# teensyRecord.net
KiCad netlist of a schematic drawn in Altium Designer
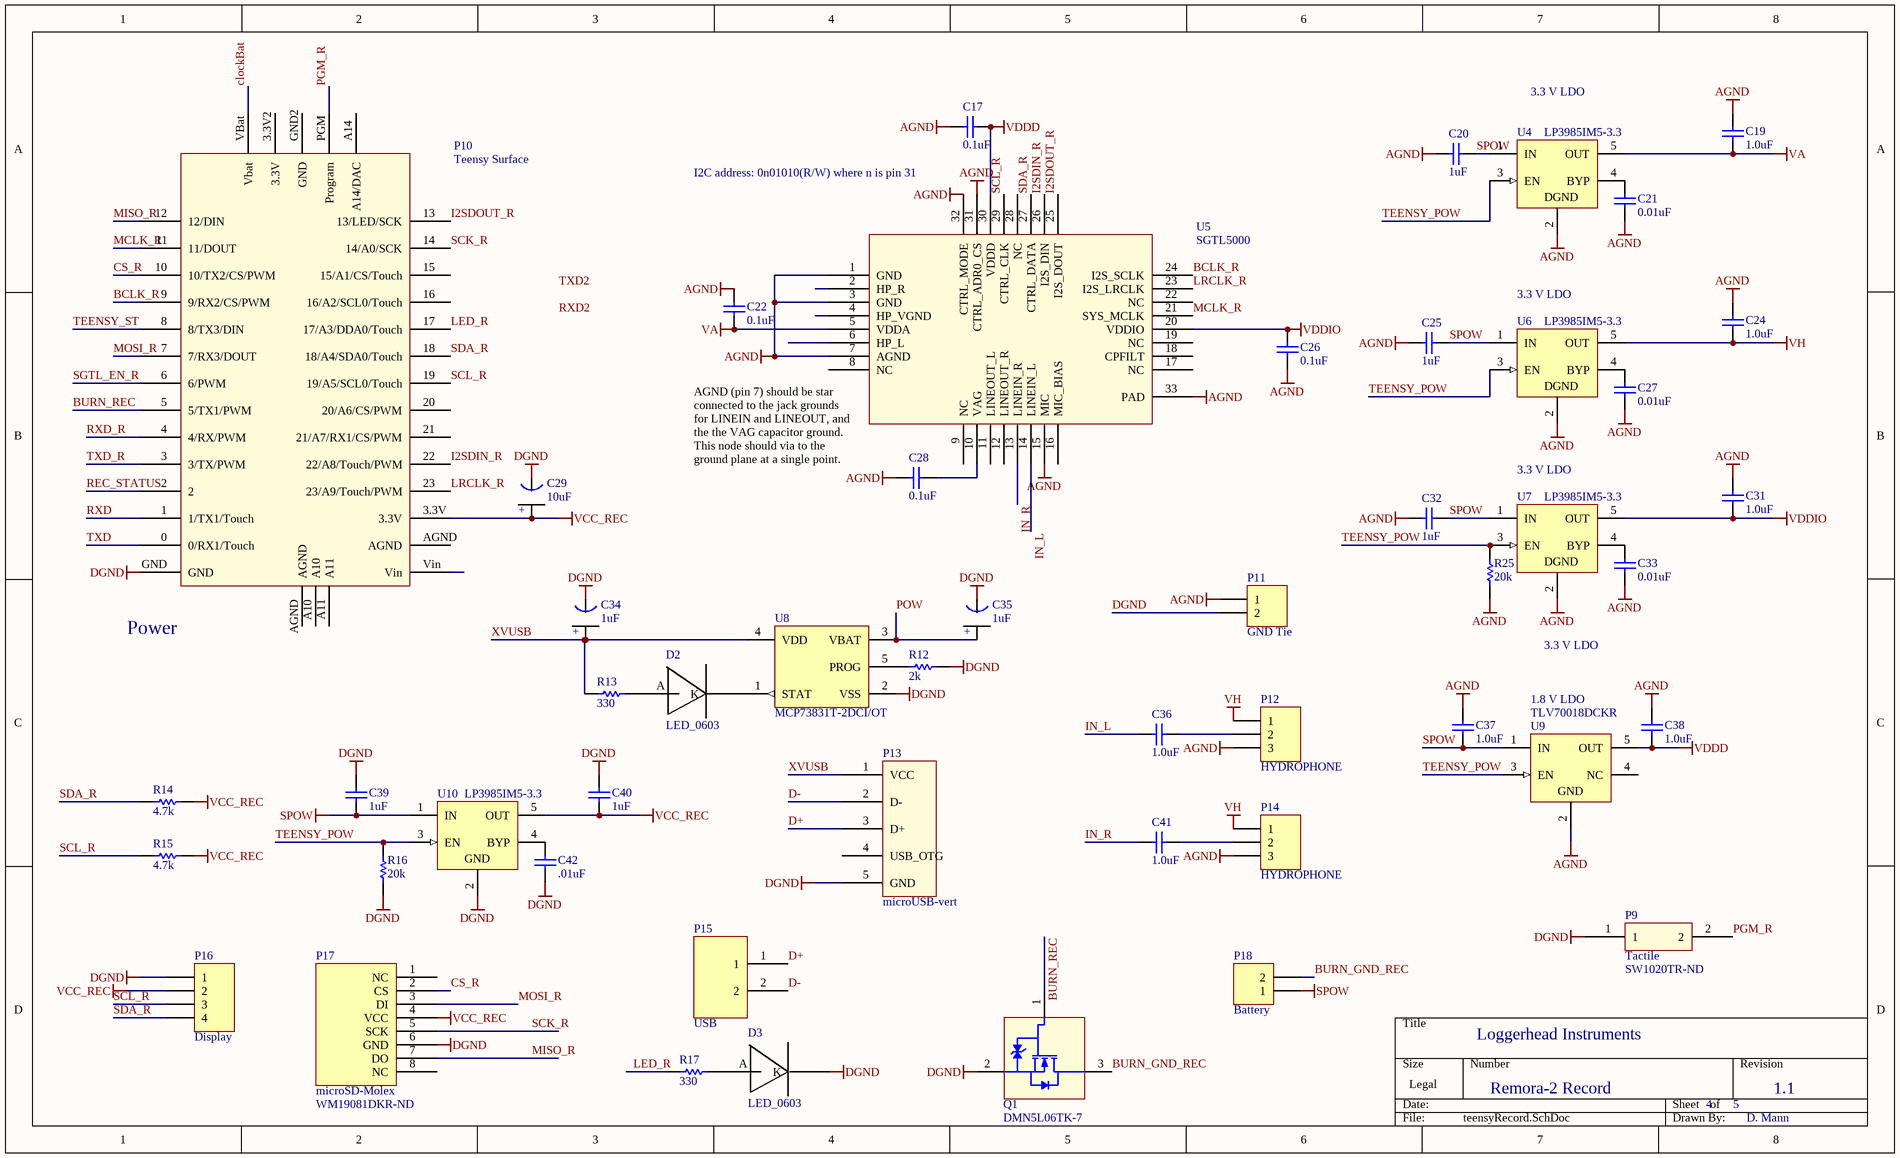
[diagram p0: teensyRecord.SchDoc]

(export (version "E")
  (design (tool "Eeschema 10.0.6"))
  (components
    (comp (ref "C17")
      (value "0.1uF")
      (footprint "0402")
      (description "Ceramic Chip Capacitor - Standard")
      (fields (field (name "PUBLISHER") "Altium Limited"))
      (libsource (lib "KEMET Chip Capacitor") (part "C0402"))
    )
    (comp (ref "C19")
      (value "1.0uF")
      (footprint "0402")
      (description "Ceramic Chip Capacitor - Standard")
      (fields (field (name "PUBLISHER") "Altium Limited"))
      (libsource (lib "KEMET Chip Capacitor") (part "C0402"))
    )
    (comp (ref "C20")
      (value "1uF")
      (footprint "0402")
      (description "Ceramic Chip Capacitor - Standard")
      (fields (field (name "PUBLISHER") "Altium Limited"))
      (libsource (lib "KEMET Chip Capacitor") (part "C0402"))
    )
    (comp (ref "C21")
      (value "0.01uF")
      (footprint "0402")
      (description "Ceramic Chip Capacitor - Standard")
      (fields (field (name "PUBLISHER") "Altium Limited"))
      (libsource (lib "KEMET Chip Capacitor") (part "C0402"))
    )
    (comp (ref "C22")
      (value "0.1uF")
      (footprint "0402")
      (description "Ceramic Chip Capacitor - Standard")
      (fields (field (name "PUBLISHER") "Altium Limited"))
      (libsource (lib "KEMET Chip Capacitor") (part "C0402"))
    )
    (comp (ref "C24")
      (value "1.0uF")
      (footprint "0402")
      (description "Ceramic Chip Capacitor - Standard")
      (fields (field (name "PUBLISHER") "Altium Limited"))
      (libsource (lib "KEMET Chip Capacitor") (part "C0402"))
    )
    (comp (ref "C25")
      (value "1uF")
      (footprint "0402")
      (description "Ceramic Chip Capacitor - Standard")
      (fields (field (name "PUBLISHER") "Altium Limited"))
      (libsource (lib "KEMET Chip Capacitor") (part "C0402"))
    )
    (comp (ref "C26")
      (value "0.1uF")
      (footprint "0402")
      (description "Ceramic Chip Capacitor - Standard")
      (fields (field (name "PUBLISHER") "Altium Limited"))
      (libsource (lib "KEMET Chip Capacitor") (part "C0402"))
    )
    (comp (ref "C27")
      (value "0.01uF")
      (footprint "0402")
      (description "Ceramic Chip Capacitor - Standard")
      (fields (field (name "PUBLISHER") "Altium Limited"))
      (libsource (lib "KEMET Chip Capacitor") (part "C0402"))
    )
    (comp (ref "C28")
      (value "0.1uF")
      (footprint "0402")
      (description "Ceramic Chip Capacitor - Standard")
      (fields (field (name "PUBLISHER") "Altium Limited"))
      (libsource (lib "KEMET Chip Capacitor") (part "C0402"))
    )
    (comp (ref "C29") (value "10uF") (footprint "Tant0805") (libsource (lib "Loggerhead") (part "Tant0805")))
    (comp (ref "C31")
      (value "1.0uF")
      (footprint "0402")
      (description "Ceramic Chip Capacitor - Standard")
      (fields (field (name "PUBLISHER") "Altium Limited"))
      (libsource (lib "KEMET Chip Capacitor") (part "C0402"))
    )
    (comp (ref "C32")
      (value "1uF")
      (footprint "0402")
      (description "Ceramic Chip Capacitor - Standard")
      (fields (field (name "PUBLISHER") "Altium Limited"))
      (libsource (lib "KEMET Chip Capacitor") (part "C0402"))
    )
    (comp (ref "C33")
      (value "0.01uF")
      (footprint "0402")
      (description "Ceramic Chip Capacitor - Standard")
      (fields (field (name "PUBLISHER") "Altium Limited"))
      (libsource (lib "KEMET Chip Capacitor") (part "C0402"))
    )
    (comp (ref "C34") (value "1uF") (footprint "Tant0805") (libsource (lib "Loggerhead") (part "Tant0805")))
    (comp (ref "C35") (value "1uF") (footprint "Tant0805") (libsource (lib "Loggerhead") (part "Tant0805")))
    (comp (ref "C36")
      (value "1.0uF")
      (footprint "0402")
      (description "Ceramic Chip Capacitor - Standard")
      (fields (field (name "PUBLISHER") "Altium Limited"))
      (libsource (lib "KEMET Chip Capacitor") (part "C0402"))
    )
    (comp (ref "C37")
      (value "1.0uF")
      (footprint "0402")
      (description "Ceramic Chip Capacitor - Standard")
      (fields (field (name "PUBLISHER") "Altium Limited"))
      (libsource (lib "KEMET Chip Capacitor") (part "C0402"))
    )
    (comp (ref "C38")
      (value "1.0uF")
      (footprint "0402")
      (description "Ceramic Chip Capacitor - Standard")
      (fields (field (name "PUBLISHER") "Altium Limited"))
      (libsource (lib "KEMET Chip Capacitor") (part "C0402"))
    )
    (comp (ref "C39")
      (value "1uF")
      (footprint "0402")
      (description "Ceramic Chip Capacitor - Standard")
      (fields (field (name "PUBLISHER") "Altium Limited"))
      (libsource (lib "KEMET Chip Capacitor") (part "C0402"))
    )
    (comp (ref "C40")
      (value "1uF")
      (footprint "0402")
      (description "Ceramic Chip Capacitor - Standard")
      (fields (field (name "PUBLISHER") "Altium Limited"))
      (libsource (lib "KEMET Chip Capacitor") (part "C0402"))
    )
    (comp (ref "C41")
      (value "1.0uF")
      (footprint "0402")
      (description "Ceramic Chip Capacitor - Standard")
      (fields (field (name "PUBLISHER") "Altium Limited"))
      (libsource (lib "KEMET Chip Capacitor") (part "C0402"))
    )
    (comp (ref "C42")
      (value ".01uF")
      (footprint "0402")
      (description "Ceramic Chip Capacitor - Standard")
      (fields (field (name "PUBLISHER") "Altium Limited"))
      (libsource (lib "KEMET Chip Capacitor") (part "C0402"))
    )
    (comp (ref "D2")
      (value "LED_0603")
      (footprint "Diode0603")
      (libsource (lib "Loggerhead") (part "LED_0603"))
    )
    (comp (ref "D3")
      (value "LED_0603")
      (footprint "Diode0603")
      (libsource (lib "Loggerhead") (part "LED_0603"))
    )
    (comp (ref "P9")
      (value "Tactile")
      (footprint "Tactile-B3U-1000")
      (fields (field (name "SUPPLIER PART NUMBER 1") "SW1020TR-ND"))
      (libsource (lib "Loggerhead") (part "Tactile_B3U-1000"))
    )
    (comp (ref "P10")
      (value "Teensy Surface")
      (footprint "TEENSY3.2_surface_mount")
      (libsource (lib "Teensy") (part "Teensy3.2_surface_mount"))
    )
    (comp (ref "P11")
      (value "GND Tie")
      (footprint "HDR1X2")
      (description "Header, 2-Pin")
      (fields (field (name "PUBLISHER") "Altium Limited"))
      (libsource (lib "Miscellaneous Connectors") (part "Header 2"))
    )
    (comp (ref "P12")
      (value "HYDROPHONE")
      (footprint "HDR1X3")
      (description "Header, 3-Pin")
      (fields (field (name "PUBLISHER") "Altium Limited"))
      (libsource (lib "Miscellaneous Connectors") (part "Header 3"))
    )
    (comp (ref "P13")
      (value "microUSB-vert")
      (footprint "MICROUSB-VERT")
      (description "Molex 105133-0011")
      (libsource (lib "Loggerhead") (part "microUSB-vert"))
    )
    (comp (ref "P14")
      (value "HYDROPHONE")
      (footprint "HDR1X3")
      (description "Header, 3-Pin")
      (fields (field (name "PUBLISHER") "Altium Limited"))
      (libsource (lib "Miscellaneous Connectors") (part "Header 3"))
    )
    (comp (ref "P15")
      (value "USB")
      (footprint "HDR_2x1_2mm")
      (description "Charging Connector")
      (libsource (lib "Loggerhead") (part "HDR_2x1_2mm"))
    )
    (comp (ref "P16")
      (value "Display")
      (footprint "HDR1X4")
      (description "Header, 4-Pin")
      (fields (field (name "PUBLISHER") "Altium Limited"))
      (libsource (lib "Miscellaneous Connectors") (part "Header 4"))
    )
    (comp (ref "P17")
      (value "microSD-Molex")
      (footprint "microSD_Molex_hinged")
      (fields (field (name "SUPPLIER PART NUMBER 1") "WM19081DKR-ND"))
      (libsource (lib "Loggerhead") (part "microSD_Molex_hinged"))
    )
    (comp (ref "P18")
      (value "Battery")
      (footprint "HDR1X2")
      (description "Header, 2-Pin")
      (fields (field (name "PUBLISHER") "Altium Limited"))
      (libsource (lib "") (part "Header 2_1"))
    )
    (comp (ref "Q1")
      (value "DMN5L06TK-7")
      (footprint "SOT-523")
      (description "Ultra-low leakage Enhanced MOSFET")
      (fields
        (field (name "CREATOR AND DATE") "Will Flanery 2010-09-02")
        (field (name "FOOTPRINT VERIFIED BY") "*")
        (field (name "SCHEMATIC VERIFIED BY") "*")
        (field (name "VENDOR INFO VERIFIED BY") "*")
      )
      (libsource (lib "Flanery") (part "FET DMN5L06TK-7"))
    )
    (comp (ref "R12")
      (value "2k")
      (footprint "3-0603")
      (fields (field (name "PUBLISHER") "Altium Limited"))
      (libsource (lib "Panasonic Resistor") (part "ERJ3RK"))
    )
    (comp (ref "R13")
      (value "330")
      (footprint "3-0603")
      (fields (field (name "PUBLISHER") "Altium Limited"))
      (libsource (lib "Panasonic Resistor") (part "ERJ3RK"))
    )
    (comp (ref "R14")
      (value "4.7k")
      (footprint "3-0603")
      (fields (field (name "PUBLISHER") "Altium Limited"))
      (libsource (lib "Panasonic Resistor") (part "ERJ3RK"))
    )
    (comp (ref "R15")
      (value "4.7k")
      (footprint "3-0603")
      (fields (field (name "PUBLISHER") "Altium Limited"))
      (libsource (lib "Panasonic Resistor") (part "ERJ3RK"))
    )
    (comp (ref "R16")
      (value "20k")
      (footprint "3-0603")
      (fields (field (name "PUBLISHER") "Altium Limited"))
      (libsource (lib "Panasonic Resistor") (part "ERJ3RK"))
    )
    (comp (ref "R17")
      (value "330")
      (footprint "3-0603")
      (fields (field (name "PUBLISHER") "Altium Limited"))
      (libsource (lib "Panasonic Resistor") (part "ERJ3RK"))
    )
    (comp (ref "R25")
      (value "20k")
      (footprint "3-0603")
      (fields (field (name "PUBLISHER") "Altium Limited"))
      (libsource (lib "Panasonic Resistor") (part "ERJ3RK"))
    )
    (comp (ref "U4")
      (value "LP3985IM5-3.3")
      (footprint "MF05A_N")
      (description "Micropower, 150mA Low-Noise Ultra Low-Dropout CMOS Voltage Regulator")
      (fields
        (field (name "MANUFACTURER") "National Semiconductor")
        (field (name "DIGIKEYPARTNUMBER") "LP3985IM5-3.3CT-ND")
        (field (name "PUBLISHER") "Altium Limited")
      )
      (libsource (lib "NSC LDO") (part "LP3985IM5-3.3"))
    )
    (comp (ref "U5") (value "SGTL5000") (footprint "QFN32") (libsource (lib "Loggerhead") (part "SGTL5000")))
    (comp (ref "U6")
      (value "LP3985IM5-3.3")
      (footprint "MF05A_N")
      (description "Micropower, 150mA Low-Noise Ultra Low-Dropout CMOS Voltage Regulator")
      (fields
        (field (name "MANUFACTURER") "National Semiconductor")
        (field (name "DIGIKEYPARTNUMBER") "LP3985IM5-3.3CT-ND")
        (field (name "PUBLISHER") "Altium Limited")
      )
      (libsource (lib "NSC LDO") (part "LP3985IM5-3.3"))
    )
    (comp (ref "U7")
      (value "LP3985IM5-3.3")
      (footprint "MF05A_N")
      (description "Micropower, 150mA Low-Noise Ultra Low-Dropout CMOS Voltage Regulator")
      (fields
        (field (name "MANUFACTURER") "National Semiconductor")
        (field (name "DIGIKEYPARTNUMBER") "LP3985IM5-3.3CT-ND")
        (field (name "PUBLISHER") "Altium Limited")
      )
      (libsource (lib "NSC LDO") (part "LP3985IM5-3.3"))
    )
    (comp (ref "U8")
      (value "MCP73831T-2DCI/OT")
      (footprint "SOT-23-OT5_N")
      (libsource (lib "Microchip Power Management Battery Management") (part "MCP73831T-2DCI/OT"))
    )
    (comp (ref "U9")
      (value "TLV70018DCKR")
      (footprint "TI-DCK5_V")
      (fields (field (name "MANUFACTURER") "Texas Instruments"))
      (libsource (lib "TI Power Management Linear Regulator Single Channel LDO (0-350mA)") (part "TLV70018DCKR"))
    )
    (comp (ref "U10")
      (value "LP3985IM5-3.3")
      (footprint "MF05A_N")
      (description "Micropower, 150mA Low-Noise Ultra Low-Dropout CMOS Voltage Regulator")
      (fields
        (field (name "MANUFACTURER") "National Semiconductor")
        (field (name "DIGIKEYPARTNUMBER") "LP3985IM5-3.3CT-ND")
        (field (name "PUBLISHER") "Altium Limited")
      )
      (libsource (lib "NSC LDO") (part "LP3985IM5-3.3"))
    )
  )
  (nets
    (net (code "1") (name "/BCLK_R") (class "Default")
      (node (ref "P10") (pin "9") (pinfunction "9/RX2/CS/PWM_9") (pintype "passive"))
      (node (ref "U5") (pin "24") (pinfunction "I2S_SCLK_24") (pintype "passive"))
    )
    (net (code "2") (name "/BURN_GND_REC") (class "Default")
      (node (ref "P18") (pin "2") (pinfunction "2_2") (pintype "passive"))
      (node (ref "Q1") (pin "3") (pinfunction "D_3") (pintype "passive"))
    )
    (net (code "3") (name "/BURN_REC") (class "Default")
      (node (ref "P10") (pin "5") (pinfunction "5/TX1/PWM_5") (pintype "passive"))
      (node (ref "Q1") (pin "1") (pinfunction "G_1") (pintype "passive"))
    )
    (net (code "4") (name "/CS_R") (class "Default")
      (node (ref "P10") (pin "10") (pinfunction "10/TX2/CS/PWM_10") (pintype "passive"))
      (node (ref "P17") (pin "2") (pinfunction "CS_2") (pintype "passive"))
    )
    (net (code "5") (name "/D+") (class "Default")
      (node (ref "P13") (pin "3") (pinfunction "D+_3") (pintype "passive"))
      (node (ref "P15") (pin "1") (pinfunction "1_1") (pintype "passive"))
    )
    (net (code "6") (name "/D-") (class "Default")
      (node (ref "P13") (pin "2") (pinfunction "D-_2") (pintype "passive"))
      (node (ref "P15") (pin "2") (pinfunction "2_2") (pintype "passive"))
    )
    (net (code "7") (name "/I2SDIN_R") (class "Default")
      (node (ref "P10") (pin "22") (pinfunction "22/A8/Touch/PWM_22") (pintype "passive"))
      (node (ref "U5") (pin "26") (pinfunction "I2S_DIN_26") (pintype "passive"))
    )
    (net (code "8") (name "/I2SDOUT_R") (class "Default")
      (node (ref "P10") (pin "13") (pinfunction "13/LED/SCK_13") (pintype "passive"))
      (node (ref "U5") (pin "25") (pinfunction "I2S_DOUT_25") (pintype "passive"))
    )
    (net (code "9") (name "/IN_L") (class "Default")
      (node (ref "C36") (pin "2") (pinfunction "2_2") (pintype "passive"))
      (node (ref "U5") (pin "14") (pinfunction "LINEIN_L_14") (pintype "passive"))
    )
    (net (code "10") (name "/IN_R") (class "Default")
      (node (ref "C41") (pin "2") (pinfunction "2_2") (pintype "passive"))
      (node (ref "U5") (pin "13") (pinfunction "LINEIN_R_13") (pintype "passive"))
    )
    (net (code "11") (name "/LED_R") (class "Default")
      (node (ref "P10") (pin "17") (pinfunction "17/A3/DDA0/Touch_17") (pintype "passive"))
      (node (ref "R17") (pin "1") (pinfunction "1_1") (pintype "passive"))
    )
    (net (code "12") (name "/LRCLK_R") (class "Default")
      (node (ref "P10") (pin "23") (pinfunction "23/A9/Touch/PWM_23") (pintype "passive"))
      (node (ref "U5") (pin "23") (pinfunction "I2S_LRCLK_23") (pintype "passive"))
    )
    (net (code "13") (name "/MCLK_R") (class "Default")
      (node (ref "P10") (pin "11") (pinfunction "11/DOUT_11") (pintype "passive"))
      (node (ref "U5") (pin "21") (pinfunction "SYS_MCLK_21") (pintype "passive"))
    )
    (net (code "14") (name "/MISO_R") (class "Default")
      (node (ref "P10") (pin "12") (pinfunction "12/DIN_12") (pintype "passive"))
      (node (ref "P17") (pin "7") (pinfunction "DO_7") (pintype "passive"))
    )
    (net (code "15") (name "/MOSI_R") (class "Default")
      (node (ref "P10") (pin "7") (pinfunction "7/RX3/DOUT_7") (pintype "passive"))
      (node (ref "P17") (pin "3") (pinfunction "DI_3") (pintype "passive"))
    )
    (net (code "16") (name "/PGM_R") (class "Default")
      (node (ref "P10") (pin "PGM") (pinfunction "Program_PGM") (pintype "passive"))
      (node (ref "P9") (pin "2") (pinfunction "2_2") (pintype "passive"))
    )
    (net (code "17") (name "/POW") (class "Default")
      (node (ref "C35") (pin "2") (pinfunction "+_2") (pintype "passive"))
      (node (ref "U8") (pin "3") (pinfunction "VBAT_3") (pintype "power_in"))
    )
    (net (code "18") (name "/REC_STATUS") (class "Default")
      (node (ref "P10") (pin "2") (pinfunction "2_2") (pintype "passive"))
    )
    (net (code "19") (name "/RXD") (class "Default")
      (node (ref "P10") (pin "1") (pinfunction "1/TX1/Touch_1") (pintype "passive"))
    )
    (net (code "21") (name "/RXD_R") (class "Default")
      (node (ref "P10") (pin "4") (pinfunction "4/RX/PWM_4") (pintype "passive"))
    )
    (net (code "22") (name "/SCK_R") (class "Default")
      (node (ref "P10") (pin "14") (pinfunction "14/A0/SCK_14") (pintype "passive"))
      (node (ref "P17") (pin "5") (pinfunction "SCK_5") (pintype "passive"))
    )
    (net (code "23") (name "/SCL_R") (class "Default")
      (node (ref "P10") (pin "19") (pinfunction "19/A5/SCL0/Touch_19") (pintype "passive"))
      (node (ref "P16") (pin "3") (pinfunction "3_3") (pintype "passive"))
      (node (ref "R15") (pin "1") (pinfunction "1_1") (pintype "passive"))
      (node (ref "U5") (pin "29") (pinfunction "CTRL_CLK_29") (pintype "passive"))
    )
    (net (code "24") (name "/SDA_R") (class "Default")
      (node (ref "P10") (pin "18") (pinfunction "18/A4/SDA0/Touch_18") (pintype "passive"))
      (node (ref "P16") (pin "4") (pinfunction "4_4") (pintype "passive"))
      (node (ref "R14") (pin "1") (pinfunction "1_1") (pintype "passive"))
      (node (ref "U5") (pin "27") (pinfunction "CTRL_DATA_27") (pintype "passive"))
    )
    (net (code "25") (name "/SGTL_EN_R") (class "Default")
      (node (ref "P10") (pin "6") (pinfunction "6/PWM_6") (pintype "passive"))
    )
    (net (code "26") (name "/TEENSY_POW") (class "Default")
      (node (ref "R16") (pin "2") (pinfunction "2_2") (pintype "passive"))
      (node (ref "R25") (pin "1") (pinfunction "1_1") (pintype "passive"))
      (node (ref "U10") (pin "3") (pinfunction "EN_3") (pintype "input"))
      (node (ref "U4") (pin "3") (pinfunction "EN_3") (pintype "input"))
      (node (ref "U6") (pin "3") (pinfunction "EN_3") (pintype "input"))
      (node (ref "U7") (pin "3") (pinfunction "EN_3") (pintype "input"))
      (node (ref "U9") (pin "3") (pinfunction "EN_3") (pintype "input"))
    )
    (net (code "27") (name "/TEENSY_ST") (class "Default")
      (node (ref "P10") (pin "8") (pinfunction "8/TX3/DIN_8") (pintype "passive"))
    )
    (net (code "28") (name "/TXD") (class "Default")
      (node (ref "P10") (pin "0") (pinfunction "0/RX1/Touch_0") (pintype "passive"))
    )
    (net (code "30") (name "/TXD_R") (class "Default")
      (node (ref "P10") (pin "3") (pinfunction "3/TX/PWM_3") (pintype "passive"))
    )
    (net (code "31") (name "/XVUSB") (class "Default")
      (node (ref "C34") (pin "2") (pinfunction "+_2") (pintype "passive"))
      (node (ref "P13") (pin "1") (pinfunction "VCC_1") (pintype "passive"))
      (node (ref "R13") (pin "1") (pinfunction "1_1") (pintype "passive"))
      (node (ref "U8") (pin "4") (pinfunction "VDD_4") (pintype "power_in"))
    )
    (net (code "32") (name "/clockBat") (class "Default")
      (node (ref "P10") (pin "VBat") (pinfunction "Vbat_VBat") (pintype "passive"))
    )
    (net (code "33") (name "AGND") (class "Default")
      (node (ref "C17") (pin "2") (pinfunction "2_2") (pintype "passive"))
      (node (ref "C19") (pin "2") (pinfunction "2_2") (pintype "passive"))
      (node (ref "C20") (pin "2") (pinfunction "2_2") (pintype "passive"))
      (node (ref "C21") (pin "2") (pinfunction "2_2") (pintype "passive"))
      (node (ref "C22") (pin "2") (pinfunction "2_2") (pintype "passive"))
      (node (ref "C24") (pin "2") (pinfunction "2_2") (pintype "passive"))
      (node (ref "C25") (pin "2") (pinfunction "2_2") (pintype "passive"))
      (node (ref "C26") (pin "2") (pinfunction "2_2") (pintype "passive"))
      (node (ref "C27") (pin "2") (pinfunction "2_2") (pintype "passive"))
      (node (ref "C28") (pin "2") (pinfunction "2_2") (pintype "passive"))
      (node (ref "C31") (pin "2") (pinfunction "2_2") (pintype "passive"))
      (node (ref "C32") (pin "2") (pinfunction "2_2") (pintype "passive"))
      (node (ref "C33") (pin "2") (pinfunction "2_2") (pintype "passive"))
      (node (ref "C37") (pin "2") (pinfunction "2_2") (pintype "passive"))
      (node (ref "C38") (pin "2") (pinfunction "2_2") (pintype "passive"))
      (node (ref "P11") (pin "1") (pinfunction "1_1") (pintype "passive"))
      (node (ref "P12") (pin "3") (pinfunction "3_3") (pintype "passive"))
      (node (ref "P14") (pin "3") (pinfunction "3_3") (pintype "passive"))
      (node (ref "R25") (pin "2") (pinfunction "2_2") (pintype "passive"))
      (node (ref "U4") (pin "2") (pinfunction "GND_2") (pintype "power_in"))
      (node (ref "U5") (pin "1") (pinfunction "GND_1") (pintype "passive"))
      (node (ref "U5") (pin "15") (pinfunction "MIC_15") (pintype "passive"))
      (node (ref "U5") (pin "3") (pinfunction "GND_3") (pintype "passive"))
      (node (ref "U5") (pin "31") (pinfunction "CTRL_ADR0_CS_31") (pintype "passive"))
      (node (ref "U5") (pin "32") (pinfunction "CTRL_MODE_32") (pintype "passive"))
      (node (ref "U5") (pin "33") (pinfunction "PAD_33") (pintype "passive"))
      (node (ref "U5") (pin "7") (pinfunction "AGND_7") (pintype "passive"))
      (node (ref "U6") (pin "2") (pinfunction "GND_2") (pintype "power_in"))
      (node (ref "U7") (pin "2") (pinfunction "GND_2") (pintype "power_in"))
      (node (ref "U9") (pin "2") (pinfunction "GND_2") (pintype "power_in"))
    )
    (net (code "34") (name "DGND") (class "Default")
      (node (ref "C29") (pin "1") (pinfunction "GND_1") (pintype "passive"))
      (node (ref "C34") (pin "1") (pinfunction "GND_1") (pintype "passive"))
      (node (ref "C35") (pin "1") (pinfunction "GND_1") (pintype "passive"))
      (node (ref "C39") (pin "2") (pinfunction "2_2") (pintype "passive"))
      (node (ref "C40") (pin "2") (pinfunction "2_2") (pintype "passive"))
      (node (ref "C42") (pin "1") (pinfunction "1_1") (pintype "passive"))
      (node (ref "D3") (pin "K") (pinfunction "K_K") (pintype "passive"))
      (node (ref "P10") (pin "GND") (pinfunction "GND_GND") (pintype "passive"))
      (node (ref "P11") (pin "2") (pinfunction "2_2") (pintype "passive"))
      (node (ref "P13") (pin "5") (pinfunction "GND_5") (pintype "passive"))
      (node (ref "P16") (pin "1") (pinfunction "1_1") (pintype "passive"))
      (node (ref "P17") (pin "6") (pinfunction "GND_6") (pintype "passive"))
      (node (ref "P9") (pin "1") (pinfunction "1_1") (pintype "passive"))
      (node (ref "Q1") (pin "2") (pinfunction "S_2") (pintype "passive"))
      (node (ref "R12") (pin "1") (pinfunction "1_1") (pintype "passive"))
      (node (ref "R16") (pin "1") (pinfunction "1_1") (pintype "passive"))
      (node (ref "U10") (pin "2") (pinfunction "GND_2") (pintype "power_in"))
      (node (ref "U8") (pin "2") (pinfunction "VSS_2") (pintype "power_in"))
    )
    (net (code "35") (name "Net-(C36-Pad1)") (class "Default")
      (node (ref "C36") (pin "1") (pinfunction "1_1") (pintype "passive"))
      (node (ref "P12") (pin "2") (pinfunction "2_2") (pintype "passive"))
    )
    (net (code "36") (name "Net-(C41-Pad1)") (class "Default")
      (node (ref "C41") (pin "1") (pinfunction "1_1") (pintype "passive"))
      (node (ref "P14") (pin "2") (pinfunction "2_2") (pintype "passive"))
    )
    (net (code "37") (name "Net-(D2-PadA)") (class "Default")
      (node (ref "D2") (pin "A") (pinfunction "A_A") (pintype "passive"))
      (node (ref "R13") (pin "2") (pinfunction "2_2") (pintype "passive"))
    )
    (net (code "38") (name "Net-(D3-PadA)") (class "Default")
      (node (ref "D3") (pin "A") (pinfunction "A_A") (pintype "passive"))
      (node (ref "R17") (pin "2") (pinfunction "2_2") (pintype "passive"))
    )
    (net (code "39") (name "Net-(U4-BYP)") (class "Default")
      (node (ref "C21") (pin "1") (pinfunction "1_1") (pintype "passive"))
      (node (ref "U4") (pin "4") (pinfunction "BYP_4") (pintype "passive"))
    )
    (net (code "40") (name "Net-(U5-VAG)") (class "Default")
      (node (ref "C28") (pin "1") (pinfunction "1_1") (pintype "passive"))
      (node (ref "U5") (pin "10") (pinfunction "VAG_10") (pintype "passive"))
    )
    (net (code "41") (name "Net-(U6-BYP)") (class "Default")
      (node (ref "C27") (pin "1") (pinfunction "1_1") (pintype "passive"))
      (node (ref "U6") (pin "4") (pinfunction "BYP_4") (pintype "passive"))
    )
    (net (code "42") (name "Net-(U7-BYP)") (class "Default")
      (node (ref "C33") (pin "1") (pinfunction "1_1") (pintype "passive"))
      (node (ref "U7") (pin "4") (pinfunction "BYP_4") (pintype "passive"))
    )
    (net (code "43") (name "Net-(U8-PROG)") (class "Default")
      (node (ref "R12") (pin "2") (pinfunction "2_2") (pintype "passive"))
      (node (ref "U8") (pin "5") (pinfunction "PROG_5") (pintype "passive"))
    )
    (net (code "44") (name "Net-(U8-STAT)") (class "Default")
      (node (ref "D2") (pin "K") (pinfunction "K_K") (pintype "passive"))
      (node (ref "U8") (pin "1") (pinfunction "STAT_1") (pintype "output"))
    )
    (net (code "45") (name "Net-(U10-BYP)") (class "Default")
      (node (ref "C42") (pin "2") (pinfunction "2_2") (pintype "passive"))
      (node (ref "U10") (pin "4") (pinfunction "BYP_4") (pintype "passive"))
    )
    (net (code "46") (name "SPOW") (class "Default")
      (node (ref "C20") (pin "1") (pinfunction "1_1") (pintype "passive"))
      (node (ref "C25") (pin "1") (pinfunction "1_1") (pintype "passive"))
      (node (ref "C32") (pin "1") (pinfunction "1_1") (pintype "passive"))
      (node (ref "C37") (pin "1") (pinfunction "1_1") (pintype "passive"))
      (node (ref "C39") (pin "1") (pinfunction "1_1") (pintype "passive"))
      (node (ref "P18") (pin "1") (pinfunction "1_1") (pintype "passive"))
      (node (ref "U10") (pin "1") (pinfunction "IN_1") (pintype "power_in"))
      (node (ref "U4") (pin "1") (pinfunction "IN_1") (pintype "power_in"))
      (node (ref "U6") (pin "1") (pinfunction "IN_1") (pintype "power_in"))
      (node (ref "U7") (pin "1") (pinfunction "IN_1") (pintype "power_in"))
      (node (ref "U9") (pin "1") (pinfunction "IN_1") (pintype "power_in"))
    )
    (net (code "47") (name "VA") (class "Default")
      (node (ref "C19") (pin "1") (pinfunction "1_1") (pintype "passive"))
      (node (ref "C22") (pin "1") (pinfunction "1_1") (pintype "passive"))
      (node (ref "U4") (pin "5") (pinfunction "OUT_5") (pintype "power_in"))
      (node (ref "U5") (pin "5") (pinfunction "VDDA_5") (pintype "passive"))
    )
    (net (code "48") (name "VCC_REC") (class "Default")
      (node (ref "C29") (pin "2") (pinfunction "+_2") (pintype "passive"))
      (node (ref "C40") (pin "1") (pinfunction "1_1") (pintype "passive"))
      (node (ref "P10") (pin "3.3V") (pinfunction "3.3V_3.3V") (pintype "passive"))
      (node (ref "P16") (pin "2") (pinfunction "2_2") (pintype "passive"))
      (node (ref "P17") (pin "4") (pinfunction "VCC_4") (pintype "passive"))
      (node (ref "R14") (pin "2") (pinfunction "2_2") (pintype "passive"))
      (node (ref "R15") (pin "2") (pinfunction "2_2") (pintype "passive"))
      (node (ref "U10") (pin "5") (pinfunction "OUT_5") (pintype "power_in"))
    )
    (net (code "49") (name "VDDD") (class "Default")
      (node (ref "C17") (pin "1") (pinfunction "1_1") (pintype "passive"))
      (node (ref "C38") (pin "1") (pinfunction "1_1") (pintype "passive"))
      (node (ref "U5") (pin "30") (pinfunction "VDDD_30") (pintype "passive"))
      (node (ref "U9") (pin "5") (pinfunction "OUT_5") (pintype "power_in"))
    )
    (net (code "50") (name "VDDIO") (class "Default")
      (node (ref "C26") (pin "1") (pinfunction "1_1") (pintype "passive"))
      (node (ref "C31") (pin "1") (pinfunction "1_1") (pintype "passive"))
      (node (ref "U5") (pin "20") (pinfunction "VDDIO_20") (pintype "passive"))
      (node (ref "U7") (pin "5") (pinfunction "OUT_5") (pintype "power_in"))
    )
    (net (code "51") (name "VH") (class "Default")
      (node (ref "C24") (pin "1") (pinfunction "1_1") (pintype "passive"))
      (node (ref "P12") (pin "1") (pinfunction "1_1") (pintype "passive"))
      (node (ref "P14") (pin "1") (pinfunction "1_1") (pintype "passive"))
      (node (ref "U6") (pin "5") (pinfunction "OUT_5") (pintype "power_in"))
    )
    (net (code "52") (name "unconnected-(P10-3.3V-Pad3.3V2)") (class "Default")
      (node (ref "P10") (pin "3.3V2") (pinfunction "3.3V_3.3V2") (pintype "passive"))
    )
    (net (code "53") (name "unconnected-(P10-15{slash}A1{slash}CS{slash}Touch-Pad15)") (class "Default")
      (node (ref "P10") (pin "15") (pinfunction "15/A1/CS/Touch_15") (pintype "passive"))
    )
    (net (code "54") (name "unconnected-(P10-16{slash}A2{slash}SCL0{slash}Touch-Pad16)") (class "Default")
      (node (ref "P10") (pin "16") (pinfunction "16/A2/SCL0/Touch_16") (pintype "passive"))
    )
    (net (code "55") (name "unconnected-(P10-20{slash}A6{slash}CS{slash}PWM-Pad20)") (class "Default")
      (node (ref "P10") (pin "20") (pinfunction "20/A6/CS/PWM_20") (pintype "passive"))
    )
    (net (code "56") (name "unconnected-(P10-21{slash}A7{slash}RX1{slash}CS{slash}PWM-Pad21)") (class "Default")
      (node (ref "P10") (pin "21") (pinfunction "21/A7/RX1/CS/PWM_21") (pintype "passive"))
    )
    (net (code "57") (name "unconnected-(P10-A14{slash}DAC-PadA14)") (class "Default")
      (node (ref "P10") (pin "A14") (pinfunction "A14/DAC_A14") (pintype "passive"))
    )
    (net (code "58") (name "unconnected-(P10-GND-PadGND2)") (class "Default")
      (node (ref "P10") (pin "GND2") (pinfunction "GND_GND2") (pintype "passive"))
    )
    (net (code "59") (name "unconnected-(P10-PadA10)") (class "Default")
      (node (ref "P10") (pin "A10") (pinfunction "A10_A10") (pintype "passive"))
    )
    (net (code "60") (name "unconnected-(P10-PadA11)") (class "Default")
      (node (ref "P10") (pin "A11") (pinfunction "A11_A11") (pintype "passive"))
    )
    (net (code "61") (name "unconnected-(P10-PadAGND)") (class "Default")
      (node (ref "P10") (pin "AGND") (pinfunction "AGND_AGND") (pintype "passive"))
    )
    (net (code "62") (name "unconnected-(P10-PadAGND)_1") (class "Default")
      (node (ref "P10") (pin "AGND") (pinfunction "AGND_AGND") (pintype "passive"))
    )
    (net (code "63") (name "unconnected-(P10-PadVin)") (class "Default")
      (node (ref "P10") (pin "Vin") (pinfunction "Vin_Vin") (pintype "passive"))
    )
    (net (code "64") (name "unconnected-(P13-USB_OTG-Pad4)") (class "Default")
      (node (ref "P13") (pin "4") (pinfunction "USB_OTG_4") (pintype "passive"))
    )
    (net (code "65") (name "unconnected-(P17-NC-Pad1)") (class "Default")
      (node (ref "P17") (pin "1") (pinfunction "NC_1") (pintype "passive"))
    )
    (net (code "66") (name "unconnected-(P17-NC-Pad8)") (class "Default")
      (node (ref "P17") (pin "8") (pinfunction "NC_8") (pintype "passive"))
    )
    (net (code "67") (name "unconnected-(U5-CPFILT-Pad18)") (class "Default")
      (node (ref "U5") (pin "18") (pinfunction "CPFILT_18") (pintype "passive"))
    )
    (net (code "68") (name "unconnected-(U5-HP_L-Pad6)") (class "Default")
      (node (ref "U5") (pin "6") (pinfunction "HP_L_6") (pintype "passive"))
    )
    (net (code "69") (name "unconnected-(U5-HP_R-Pad2)") (class "Default")
      (node (ref "U5") (pin "2") (pinfunction "HP_R_2") (pintype "passive"))
    )
    (net (code "70") (name "unconnected-(U5-HP_VGND-Pad4)") (class "Default")
      (node (ref "U5") (pin "4") (pinfunction "HP_VGND_4") (pintype "passive"))
    )
    (net (code "71") (name "unconnected-(U5-LINEOUT_L-Pad11)") (class "Default")
      (node (ref "U5") (pin "11") (pinfunction "LINEOUT_L_11") (pintype "passive"))
    )
    (net (code "72") (name "unconnected-(U5-LINEOUT_R-Pad12)") (class "Default")
      (node (ref "U5") (pin "12") (pinfunction "LINEOUT_R_12") (pintype "passive"))
    )
    (net (code "73") (name "unconnected-(U5-MIC_BIAS-Pad16)") (class "Default")
      (node (ref "U5") (pin "16") (pinfunction "MIC_BIAS_16") (pintype "passive"))
    )
    (net (code "74") (name "unconnected-(U5-NC-Pad8)") (class "Default")
      (node (ref "U5") (pin "8") (pinfunction "NC_8") (pintype "passive"))
    )
    (net (code "75") (name "unconnected-(U5-NC-Pad9)") (class "Default")
      (node (ref "U5") (pin "9") (pinfunction "NC_9") (pintype "passive"))
    )
    (net (code "76") (name "unconnected-(U5-NC-Pad17)") (class "Default")
      (node (ref "U5") (pin "17") (pinfunction "NC_17") (pintype "passive"))
    )
    (net (code "77") (name "unconnected-(U5-NC-Pad19)") (class "Default")
      (node (ref "U5") (pin "19") (pinfunction "NC_19") (pintype "passive"))
    )
    (net (code "78") (name "unconnected-(U5-NC-Pad22)") (class "Default")
      (node (ref "U5") (pin "22") (pinfunction "NC_22") (pintype "passive"))
    )
    (net (code "79") (name "unconnected-(U5-NC-Pad28)") (class "Default")
      (node (ref "U5") (pin "28") (pinfunction "NC_28") (pintype "passive"))
    )
    (net (code "80") (name "unconnected-(U9-NC-Pad4)") (class "Default")
      (node (ref "U9") (pin "4") (pinfunction "NC_4") (pintype "passive"))
    )
  )
)
